# low_filter.net
KiCad netlist of a schematic drawn in Altium Designer
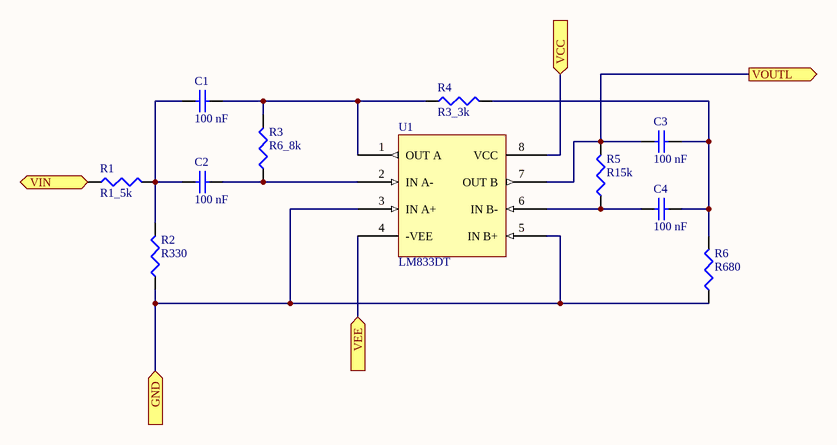
[diagram p0: low_filter.SchDoc]

(export (version "E")
  (design (tool "Eeschema 10.0.6"))
  (components
    (comp (ref "C1")
      (value "100 nF")
      (footprint "C0603")
      (description "100 nF Surface Mount Capacitor")
      (fields
        (field (name "MANUFACTURER") "Murata Electronics North America")
        (field (name "MANUFACTURER PART NUMBER") "GRM188R71C104KA01D")
      )
      (libsource (lib "Capstone Libraries") (part "C100nF"))
    )
    (comp (ref "C2")
      (value "100 nF")
      (footprint "C0603")
      (description "100 nF Surface Mount Capacitor")
      (fields
        (field (name "MANUFACTURER") "Murata Electronics North America")
        (field (name "MANUFACTURER PART NUMBER") "GRM188R71C104KA01D")
      )
      (libsource (lib "Capstone Libraries") (part "C100nF"))
    )
    (comp (ref "C3")
      (value "100 nF")
      (footprint "C0603")
      (description "100 nF Surface Mount Capacitor")
      (fields
        (field (name "MANUFACTURER") "Murata Electronics North America")
        (field (name "MANUFACTURER PART NUMBER") "GRM188R71C104KA01D")
      )
      (libsource (lib "Capstone Libraries") (part "C100nF"))
    )
    (comp (ref "C4")
      (value "100 nF")
      (footprint "C0603")
      (description "100 nF Surface Mount Capacitor")
      (fields
        (field (name "MANUFACTURER") "Murata Electronics North America")
        (field (name "MANUFACTURER PART NUMBER") "GRM188R71C104KA01D")
      )
      (libsource (lib "Capstone Libraries") (part "C100nF"))
    )
    (comp (ref "R1")
      (value "R1_5k")
      (footprint "R0603")
      (description "1.5k Ohms Surface Mount Resistor")
      (fields
        (field (name "MANUFACTURER") "Yageo")
        (field (name "MANUFACTURER PART NUMBER") "RC0603FR-071K5L")
      )
      (libsource (lib "Capstone Libraries") (part "R1_5k"))
    )
    (comp (ref "R2")
      (value "R330")
      (footprint "R0603")
      (description "330 Ohms Surface Mount Resistor")
      (fields
        (field (name "MANUFACTURER") "Yageo")
        (field (name "MANUFACTURER PART NUMBER") "RC0603FR-07330RL")
      )
      (libsource (lib "Capstone Libraries") (part "R330"))
    )
    (comp (ref "R3")
      (value "R6_8k")
      (footprint "R0603")
      (description "6.8k Ohms Surface Mount Resistor")
      (fields
        (field (name "MANUFACTURER") "Panasonic Electronic Components")
        (field (name "MANUFACTURER PART NUMBER") "ERJ-3EKF6801V")
      )
      (libsource (lib "Capstone Libraries") (part "R6_8k"))
    )
    (comp (ref "R4")
      (value "R3_3k")
      (footprint "R0603")
      (description "3.3k Ohms Surface Mount Resistor")
      (fields
        (field (name "MANUFACTURER") "Yageo")
        (field (name "MANUFACTURER PART NUMBER") "RC0603FR-073K3L")
      )
      (libsource (lib "Capstone Libraries") (part "R3_3k"))
    )
    (comp (ref "R5")
      (value "R15k")
      (footprint "R0603")
      (description "15k Ohms Surface Mount Resistor")
      (fields
        (field (name "MANUFACTURER") "Yageo")
        (field (name "MANUFACTURER PART NUMBER") "RC0603FR-0715KL")
      )
      (libsource (lib "Capstone Libraries") (part "R15k"))
    )
    (comp (ref "R6")
      (value "R680")
      (footprint "R0603")
      (description "680 Ohms Surface Mount Resistor")
      (fields
        (field (name "MANUFACTURER") "Yageo")
        (field (name "MANUFACTURER PART NUMBER") "RC0603FR-07680RL")
      )
      (libsource (lib "Capstone Libraries") (part "R680"))
    )
    (comp (ref "U1")
      (value "LM833DT")
      (footprint "soic8")
      (description "IC Dual Audio Amplifier")
      (fields (field (name "MANUFACTURER") "STMicroelectronics"))
      (libsource (lib "Capstone Libraries") (part "LM833DT"))
    )
  )
  (nets
    (net (code "1") (name "/GND") (class "Default")
      (node (ref "R2") (pin "1") (pinfunction "1_1") (pintype "passive"))
      (node (ref "R6") (pin "1") (pinfunction "1_1") (pintype "passive"))
      (node (ref "U1") (pin "3") (pinfunction "IN_A+_3") (pintype "input"))
      (node (ref "U1") (pin "5") (pinfunction "IN_B+_5") (pintype "input"))
    )
    (net (code "2") (name "/VCC") (class "Default")
      (node (ref "U1") (pin "8") (pinfunction "VCC_8") (pintype "passive"))
    )
    (net (code "3") (name "/VEE") (class "Default")
      (node (ref "U1") (pin "4") (pinfunction "-VEE_4") (pintype "passive"))
    )
    (net (code "4") (name "/VIN") (class "Default")
      (node (ref "R1") (pin "1") (pinfunction "1_1") (pintype "passive"))
    )
    (net (code "5") (name "/VOUTL") (class "Default")
      (node (ref "C3") (pin "1") (pinfunction "1_1") (pintype "passive"))
      (node (ref "R5") (pin "2") (pinfunction "2_2") (pintype "passive"))
      (node (ref "U1") (pin "7") (pinfunction "OUT_B_7") (pintype "output"))
    )
    (net (code "6") (name "Net-(C1-Pad1)") (class "Default")
      (node (ref "C1") (pin "1") (pinfunction "1_1") (pintype "passive"))
      (node (ref "C2") (pin "1") (pinfunction "1_1") (pintype "passive"))
      (node (ref "R1") (pin "2") (pinfunction "2_2") (pintype "passive"))
      (node (ref "R2") (pin "2") (pinfunction "2_2") (pintype "passive"))
    )
    (net (code "7") (name "Net-(C3-Pad2)") (class "Default")
      (node (ref "C3") (pin "2") (pinfunction "2_2") (pintype "passive"))
      (node (ref "C4") (pin "2") (pinfunction "2_2") (pintype "passive"))
      (node (ref "R4") (pin "2") (pinfunction "2_2") (pintype "passive"))
      (node (ref "R6") (pin "2") (pinfunction "2_2") (pintype "passive"))
    )
    (net (code "8") (name "Net-(U1-IN_A-)") (class "Default")
      (node (ref "C2") (pin "2") (pinfunction "2_2") (pintype "passive"))
      (node (ref "R3") (pin "1") (pinfunction "1_1") (pintype "passive"))
      (node (ref "U1") (pin "2") (pinfunction "IN_A-_2") (pintype "input"))
    )
    (net (code "9") (name "Net-(U1-IN_B-)") (class "Default")
      (node (ref "C4") (pin "1") (pinfunction "1_1") (pintype "passive"))
      (node (ref "R5") (pin "1") (pinfunction "1_1") (pintype "passive"))
      (node (ref "U1") (pin "6") (pinfunction "IN_B-_6") (pintype "input"))
    )
    (net (code "10") (name "Net-(U1-OUT_A)") (class "Default")
      (node (ref "C1") (pin "2") (pinfunction "2_2") (pintype "passive"))
      (node (ref "R3") (pin "2") (pinfunction "2_2") (pintype "passive"))
      (node (ref "R4") (pin "1") (pinfunction "1_1") (pintype "passive"))
      (node (ref "U1") (pin "1") (pinfunction "OUT_A_1") (pintype "output"))
    )
  )
)
